# Clock_Segment.net
KiCad netlist of a schematic drawn in EAGLE
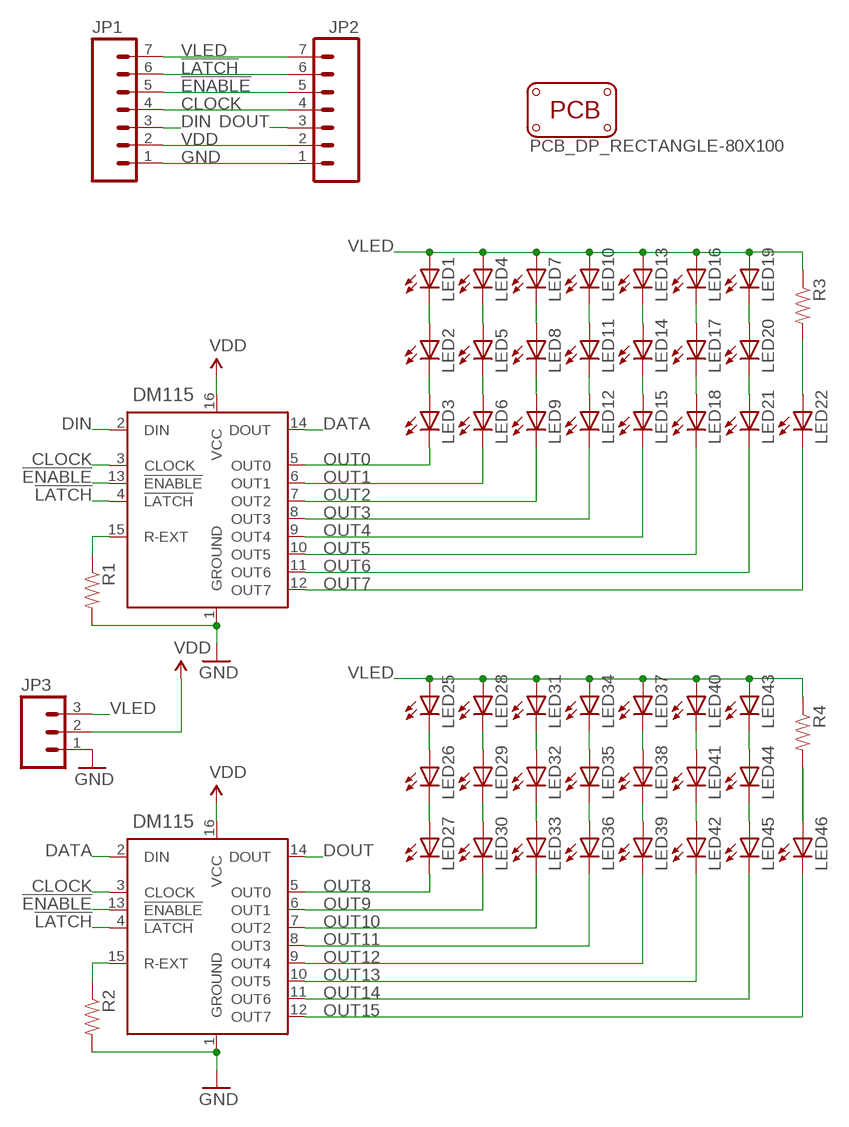
[diagram p0: schematic, sheet 1]

(export (version "E")
  (design (tool "Eeschema 10.0.6"))
  (components
    (comp (ref "JP1")
      (value "M07")
      (footprint "eagle-import:1X07")
      (libsource (lib "eagle-import") (part "M07"))
    )
    (comp (ref "JP2")
      (value "M07")
      (footprint "eagle-import:1X07")
      (libsource (lib "eagle-import") (part "M07"))
    )
    (comp (ref "JP3")
      (value "M03SCREW")
      (footprint "eagle-import:SCREWTERMINAL-3.5MM-3")
      (libsource (lib "eagle-import") (part "M03SCREW"))
    )
    (comp (ref "LED1")
      (value "LEDOVAL")
      (footprint "eagle-import:LED-OVAL")
      (libsource (lib "eagle-import") (part "LEDOVAL"))
    )
    (comp (ref "LED2")
      (value "LEDOVAL")
      (footprint "eagle-import:LED-OVAL")
      (libsource (lib "eagle-import") (part "LEDOVAL"))
    )
    (comp (ref "LED3")
      (value "LEDOVAL")
      (footprint "eagle-import:LED-OVAL")
      (libsource (lib "eagle-import") (part "LEDOVAL"))
    )
    (comp (ref "LED4")
      (value "LEDOVAL")
      (footprint "eagle-import:LED-OVAL")
      (libsource (lib "eagle-import") (part "LEDOVAL"))
    )
    (comp (ref "LED5")
      (value "LEDOVAL")
      (footprint "eagle-import:LED-OVAL")
      (libsource (lib "eagle-import") (part "LEDOVAL"))
    )
    (comp (ref "LED6")
      (value "LEDOVAL")
      (footprint "eagle-import:LED-OVAL")
      (libsource (lib "eagle-import") (part "LEDOVAL"))
    )
    (comp (ref "LED7")
      (value "LEDOVAL")
      (footprint "eagle-import:LED-OVAL")
      (libsource (lib "eagle-import") (part "LEDOVAL"))
    )
    (comp (ref "LED8")
      (value "LEDOVAL")
      (footprint "eagle-import:LED-OVAL")
      (libsource (lib "eagle-import") (part "LEDOVAL"))
    )
    (comp (ref "LED9")
      (value "LEDOVAL")
      (footprint "eagle-import:LED-OVAL")
      (libsource (lib "eagle-import") (part "LEDOVAL"))
    )
    (comp (ref "LED10")
      (value "LEDOVAL")
      (footprint "eagle-import:LED-OVAL")
      (libsource (lib "eagle-import") (part "LEDOVAL"))
    )
    (comp (ref "LED11")
      (value "LEDOVAL")
      (footprint "eagle-import:LED-OVAL")
      (libsource (lib "eagle-import") (part "LEDOVAL"))
    )
    (comp (ref "LED12")
      (value "LEDOVAL")
      (footprint "eagle-import:LED-OVAL")
      (libsource (lib "eagle-import") (part "LEDOVAL"))
    )
    (comp (ref "LED13")
      (value "LEDOVAL")
      (footprint "eagle-import:LED-OVAL")
      (libsource (lib "eagle-import") (part "LEDOVAL"))
    )
    (comp (ref "LED14")
      (value "LEDOVAL")
      (footprint "eagle-import:LED-OVAL")
      (libsource (lib "eagle-import") (part "LEDOVAL"))
    )
    (comp (ref "LED15")
      (value "LEDOVAL")
      (footprint "eagle-import:LED-OVAL")
      (libsource (lib "eagle-import") (part "LEDOVAL"))
    )
    (comp (ref "LED16")
      (value "LEDOVAL")
      (footprint "eagle-import:LED-OVAL")
      (libsource (lib "eagle-import") (part "LEDOVAL"))
    )
    (comp (ref "LED17")
      (value "LEDOVAL")
      (footprint "eagle-import:LED-OVAL")
      (libsource (lib "eagle-import") (part "LEDOVAL"))
    )
    (comp (ref "LED18")
      (value "LEDOVAL")
      (footprint "eagle-import:LED-OVAL")
      (libsource (lib "eagle-import") (part "LEDOVAL"))
    )
    (comp (ref "LED19")
      (value "LEDOVAL")
      (footprint "eagle-import:LED-OVAL")
      (libsource (lib "eagle-import") (part "LEDOVAL"))
    )
    (comp (ref "LED20")
      (value "LEDOVAL")
      (footprint "eagle-import:LED-OVAL")
      (libsource (lib "eagle-import") (part "LEDOVAL"))
    )
    (comp (ref "LED21")
      (value "LEDOVAL")
      (footprint "eagle-import:LED-OVAL")
      (libsource (lib "eagle-import") (part "LEDOVAL"))
    )
    (comp (ref "LED22")
      (value "LEDOVAL")
      (footprint "eagle-import:LED-OVAL")
      (libsource (lib "eagle-import") (part "LEDOVAL"))
    )
    (comp (ref "LED25")
      (value "LEDOVAL")
      (footprint "eagle-import:LED-OVAL")
      (libsource (lib "eagle-import") (part "LEDOVAL"))
    )
    (comp (ref "LED26")
      (value "LEDOVAL")
      (footprint "eagle-import:LED-OVAL")
      (libsource (lib "eagle-import") (part "LEDOVAL"))
    )
    (comp (ref "LED27")
      (value "LEDOVAL")
      (footprint "eagle-import:LED-OVAL")
      (libsource (lib "eagle-import") (part "LEDOVAL"))
    )
    (comp (ref "LED28")
      (value "LEDOVAL")
      (footprint "eagle-import:LED-OVAL")
      (libsource (lib "eagle-import") (part "LEDOVAL"))
    )
    (comp (ref "LED29")
      (value "LEDOVAL")
      (footprint "eagle-import:LED-OVAL")
      (libsource (lib "eagle-import") (part "LEDOVAL"))
    )
    (comp (ref "LED30")
      (value "LEDOVAL")
      (footprint "eagle-import:LED-OVAL")
      (libsource (lib "eagle-import") (part "LEDOVAL"))
    )
    (comp (ref "LED31")
      (value "LEDOVAL")
      (footprint "eagle-import:LED-OVAL")
      (libsource (lib "eagle-import") (part "LEDOVAL"))
    )
    (comp (ref "LED32")
      (value "LEDOVAL")
      (footprint "eagle-import:LED-OVAL")
      (libsource (lib "eagle-import") (part "LEDOVAL"))
    )
    (comp (ref "LED33")
      (value "LEDOVAL")
      (footprint "eagle-import:LED-OVAL")
      (libsource (lib "eagle-import") (part "LEDOVAL"))
    )
    (comp (ref "LED34")
      (value "LEDOVAL")
      (footprint "eagle-import:LED-OVAL")
      (libsource (lib "eagle-import") (part "LEDOVAL"))
    )
    (comp (ref "LED35")
      (value "LEDOVAL")
      (footprint "eagle-import:LED-OVAL")
      (libsource (lib "eagle-import") (part "LEDOVAL"))
    )
    (comp (ref "LED36")
      (value "LEDOVAL")
      (footprint "eagle-import:LED-OVAL")
      (libsource (lib "eagle-import") (part "LEDOVAL"))
    )
    (comp (ref "LED37")
      (value "LEDOVAL")
      (footprint "eagle-import:LED-OVAL")
      (libsource (lib "eagle-import") (part "LEDOVAL"))
    )
    (comp (ref "LED38")
      (value "LEDOVAL")
      (footprint "eagle-import:LED-OVAL")
      (libsource (lib "eagle-import") (part "LEDOVAL"))
    )
    (comp (ref "LED39")
      (value "LEDOVAL")
      (footprint "eagle-import:LED-OVAL")
      (libsource (lib "eagle-import") (part "LEDOVAL"))
    )
    (comp (ref "LED40")
      (value "LEDOVAL")
      (footprint "eagle-import:LED-OVAL")
      (libsource (lib "eagle-import") (part "LEDOVAL"))
    )
    (comp (ref "LED41")
      (value "LEDOVAL")
      (footprint "eagle-import:LED-OVAL")
      (libsource (lib "eagle-import") (part "LEDOVAL"))
    )
    (comp (ref "LED42")
      (value "LEDOVAL")
      (footprint "eagle-import:LED-OVAL")
      (libsource (lib "eagle-import") (part "LEDOVAL"))
    )
    (comp (ref "LED43")
      (value "LEDOVAL")
      (footprint "eagle-import:LED-OVAL")
      (libsource (lib "eagle-import") (part "LEDOVAL"))
    )
    (comp (ref "LED44")
      (value "LEDOVAL")
      (footprint "eagle-import:LED-OVAL")
      (libsource (lib "eagle-import") (part "LEDOVAL"))
    )
    (comp (ref "LED45")
      (value "LEDOVAL")
      (footprint "eagle-import:LED-OVAL")
      (libsource (lib "eagle-import") (part "LEDOVAL"))
    )
    (comp (ref "LED46")
      (value "LEDOVAL")
      (footprint "eagle-import:LED-OVAL")
      (libsource (lib "eagle-import") (part "LEDOVAL"))
    )
    (comp (ref "PCB1")
      (value "PCB_DP_RECTANGLE-80X100")
      (footprint "eagle-import:DP10080_V1")
      (libsource (lib "eagle-import") (part "PCB_DP_RECTANGLE-80X100"))
    )
    (comp (ref "R1")
      (value "RESISTORAXIAL-0.3")
      (footprint "eagle-import:AXIAL-0.3")
      (libsource (lib "eagle-import") (part "RESISTORAXIAL-0.3"))
    )
    (comp (ref "R2")
      (value "RESISTORAXIAL-0.3")
      (footprint "eagle-import:AXIAL-0.3")
      (libsource (lib "eagle-import") (part "RESISTORAXIAL-0.3"))
    )
    (comp (ref "R3")
      (value "RESISTORAXIAL-0.3")
      (footprint "eagle-import:AXIAL-0.3")
      (libsource (lib "eagle-import") (part "RESISTORAXIAL-0.3"))
    )
    (comp (ref "R4")
      (value "RESISTORAXIAL-0.3")
      (footprint "eagle-import:AXIAL-0.3")
      (libsource (lib "eagle-import") (part "RESISTORAXIAL-0.3"))
    )
    (comp (ref "U1")
      (value "DM115DIP16")
      (footprint "eagle-import:DIL16")
      (libsource (lib "eagle-import") (part "DM115DIP16"))
    )
    (comp (ref "U2")
      (value "DM115DIP16")
      (footprint "eagle-import:DIL16")
      (libsource (lib "eagle-import") (part "DM115DIP16"))
    )
  )
  (nets
    (net (code "1") (name "/CLOCK") (class "Default")
      (node (ref "JP1") (pin "4") (pinfunction "4_4") (pintype "passive"))
      (node (ref "JP2") (pin "4") (pinfunction "4_4") (pintype "passive"))
      (node (ref "U1") (pin "3") (pinfunction "CLOCK_3") (pintype "bidirectional"))
      (node (ref "U2") (pin "3") (pinfunction "CLOCK_3") (pintype "bidirectional"))
    )
    (net (code "2") (name "/DATA") (class "Default")
      (node (ref "U1") (pin "14") (pinfunction "DOUT_14") (pintype "bidirectional"))
      (node (ref "U2") (pin "2") (pinfunction "DIN_2") (pintype "bidirectional"))
    )
    (net (code "3") (name "/DIN") (class "Default")
      (node (ref "JP1") (pin "3") (pinfunction "3_3") (pintype "passive"))
      (node (ref "U1") (pin "2") (pinfunction "DIN_2") (pintype "bidirectional"))
    )
    (net (code "4") (name "/DOUT") (class "Default")
      (node (ref "JP2") (pin "3") (pinfunction "3_3") (pintype "passive"))
      (node (ref "U2") (pin "14") (pinfunction "DOUT_14") (pintype "bidirectional"))
    )
    (net (code "5") (name "/OUT0") (class "Default")
      (node (ref "LED3") (pin "CATHODE") (pinfunction "C_CATHODE") (pintype "passive"))
      (node (ref "U1") (pin "5") (pinfunction "OUT0_5") (pintype "bidirectional"))
    )
    (net (code "6") (name "/OUT1") (class "Default")
      (node (ref "LED6") (pin "CATHODE") (pinfunction "C_CATHODE") (pintype "passive"))
      (node (ref "U1") (pin "6") (pinfunction "OUT1_6") (pintype "bidirectional"))
    )
    (net (code "7") (name "/OUT2") (class "Default")
      (node (ref "LED9") (pin "CATHODE") (pinfunction "C_CATHODE") (pintype "passive"))
      (node (ref "U1") (pin "7") (pinfunction "OUT2_7") (pintype "bidirectional"))
    )
    (net (code "8") (name "/OUT3") (class "Default")
      (node (ref "LED12") (pin "CATHODE") (pinfunction "C_CATHODE") (pintype "passive"))
      (node (ref "U1") (pin "8") (pinfunction "OUT3_8") (pintype "bidirectional"))
    )
    (net (code "9") (name "/OUT4") (class "Default")
      (node (ref "LED15") (pin "CATHODE") (pinfunction "C_CATHODE") (pintype "passive"))
      (node (ref "U1") (pin "9") (pinfunction "OUT4_9") (pintype "bidirectional"))
    )
    (net (code "10") (name "/OUT5") (class "Default")
      (node (ref "LED18") (pin "CATHODE") (pinfunction "C_CATHODE") (pintype "passive"))
      (node (ref "U1") (pin "10") (pinfunction "OUT5_10") (pintype "bidirectional"))
    )
    (net (code "11") (name "/OUT6") (class "Default")
      (node (ref "LED21") (pin "CATHODE") (pinfunction "C_CATHODE") (pintype "passive"))
      (node (ref "U1") (pin "11") (pinfunction "OUT6_11") (pintype "bidirectional"))
    )
    (net (code "12") (name "/OUT7") (class "Default")
      (node (ref "LED22") (pin "CATHODE") (pinfunction "C_CATHODE") (pintype "passive"))
      (node (ref "U1") (pin "12") (pinfunction "OUT7_12") (pintype "bidirectional"))
    )
    (net (code "13") (name "/OUT8") (class "Default")
      (node (ref "LED27") (pin "CATHODE") (pinfunction "C_CATHODE") (pintype "passive"))
      (node (ref "U2") (pin "5") (pinfunction "OUT0_5") (pintype "bidirectional"))
    )
    (net (code "14") (name "/OUT9") (class "Default")
      (node (ref "LED30") (pin "CATHODE") (pinfunction "C_CATHODE") (pintype "passive"))
      (node (ref "U2") (pin "6") (pinfunction "OUT1_6") (pintype "bidirectional"))
    )
    (net (code "15") (name "/OUT10") (class "Default")
      (node (ref "LED33") (pin "CATHODE") (pinfunction "C_CATHODE") (pintype "passive"))
      (node (ref "U2") (pin "7") (pinfunction "OUT2_7") (pintype "bidirectional"))
    )
    (net (code "16") (name "/OUT11") (class "Default")
      (node (ref "LED36") (pin "CATHODE") (pinfunction "C_CATHODE") (pintype "passive"))
      (node (ref "U2") (pin "8") (pinfunction "OUT3_8") (pintype "bidirectional"))
    )
    (net (code "17") (name "/OUT12") (class "Default")
      (node (ref "LED39") (pin "CATHODE") (pinfunction "C_CATHODE") (pintype "passive"))
      (node (ref "U2") (pin "9") (pinfunction "OUT4_9") (pintype "bidirectional"))
    )
    (net (code "18") (name "/OUT13") (class "Default")
      (node (ref "LED42") (pin "CATHODE") (pinfunction "C_CATHODE") (pintype "passive"))
      (node (ref "U2") (pin "10") (pinfunction "OUT5_10") (pintype "bidirectional"))
    )
    (net (code "19") (name "/OUT14") (class "Default")
      (node (ref "LED45") (pin "CATHODE") (pinfunction "C_CATHODE") (pintype "passive"))
      (node (ref "U2") (pin "11") (pinfunction "OUT6_11") (pintype "bidirectional"))
    )
    (net (code "20") (name "/OUT15") (class "Default")
      (node (ref "LED46") (pin "CATHODE") (pinfunction "C_CATHODE") (pintype "passive"))
      (node (ref "U2") (pin "12") (pinfunction "OUT7_12") (pintype "bidirectional"))
    )
    (net (code "21") (name "/VLED") (class "Default")
      (node (ref "JP1") (pin "7") (pinfunction "7_7") (pintype "passive"))
      (node (ref "JP2") (pin "7") (pinfunction "7_7") (pintype "passive"))
      (node (ref "JP3") (pin "3") (pinfunction "3_3") (pintype "passive"))
      (node (ref "LED1") (pin "ANODE") (pinfunction "A_ANODE") (pintype "passive"))
      (node (ref "LED10") (pin "ANODE") (pinfunction "A_ANODE") (pintype "passive"))
      (node (ref "LED13") (pin "ANODE") (pinfunction "A_ANODE") (pintype "passive"))
      (node (ref "LED16") (pin "ANODE") (pinfunction "A_ANODE") (pintype "passive"))
      (node (ref "LED19") (pin "ANODE") (pinfunction "A_ANODE") (pintype "passive"))
      (node (ref "LED25") (pin "ANODE") (pinfunction "A_ANODE") (pintype "passive"))
      (node (ref "LED28") (pin "ANODE") (pinfunction "A_ANODE") (pintype "passive"))
      (node (ref "LED31") (pin "ANODE") (pinfunction "A_ANODE") (pintype "passive"))
      (node (ref "LED34") (pin "ANODE") (pinfunction "A_ANODE") (pintype "passive"))
      (node (ref "LED37") (pin "ANODE") (pinfunction "A_ANODE") (pintype "passive"))
      (node (ref "LED4") (pin "ANODE") (pinfunction "A_ANODE") (pintype "passive"))
      (node (ref "LED40") (pin "ANODE") (pinfunction "A_ANODE") (pintype "passive"))
      (node (ref "LED43") (pin "ANODE") (pinfunction "A_ANODE") (pintype "passive"))
      (node (ref "LED7") (pin "ANODE") (pinfunction "A_ANODE") (pintype "passive"))
      (node (ref "R3") (pin "P$1") (pinfunction "1_P$1") (pintype "passive"))
      (node (ref "R4") (pin "P$1") (pinfunction "1_P$1") (pintype "passive"))
    )
    (net (code "22") (name "/~{ENABLE}") (class "Default")
      (node (ref "JP1") (pin "5") (pinfunction "5_5") (pintype "passive"))
      (node (ref "JP2") (pin "5") (pinfunction "5_5") (pintype "passive"))
      (node (ref "U1") (pin "13") (pinfunction "~{ENABLE}_13") (pintype "bidirectional"))
      (node (ref "U2") (pin "13") (pinfunction "~{ENABLE}_13") (pintype "bidirectional"))
    )
    (net (code "23") (name "/~{LATCH}") (class "Default")
      (node (ref "JP1") (pin "6") (pinfunction "6_6") (pintype "passive"))
      (node (ref "JP2") (pin "6") (pinfunction "6_6") (pintype "passive"))
      (node (ref "U1") (pin "4") (pinfunction "~{LATCH}_4") (pintype "bidirectional"))
      (node (ref "U2") (pin "4") (pinfunction "~{LATCH}_4") (pintype "bidirectional"))
    )
    (net (code "24") (name "GND") (class "Default")
      (node (ref "JP1") (pin "1") (pinfunction "1_1") (pintype "passive"))
      (node (ref "JP2") (pin "1") (pinfunction "1_1") (pintype "passive"))
      (node (ref "JP3") (pin "1") (pinfunction "1_1") (pintype "passive"))
      (node (ref "R1") (pin "P$2") (pinfunction "2_P$2") (pintype "passive"))
      (node (ref "R2") (pin "P$2") (pinfunction "2_P$2") (pintype "passive"))
      (node (ref "U1") (pin "1") (pinfunction "GROUND_1") (pintype "bidirectional"))
      (node (ref "U2") (pin "1") (pinfunction "GROUND_1") (pintype "bidirectional"))
    )
    (net (code "25") (name "Net-(LED1-C)") (class "Default")
      (node (ref "LED1") (pin "CATHODE") (pinfunction "C_CATHODE") (pintype "passive"))
      (node (ref "LED2") (pin "ANODE") (pinfunction "A_ANODE") (pintype "passive"))
    )
    (net (code "26") (name "Net-(LED2-C)") (class "Default")
      (node (ref "LED2") (pin "CATHODE") (pinfunction "C_CATHODE") (pintype "passive"))
      (node (ref "LED3") (pin "ANODE") (pinfunction "A_ANODE") (pintype "passive"))
    )
    (net (code "27") (name "Net-(LED4-C)") (class "Default")
      (node (ref "LED4") (pin "CATHODE") (pinfunction "C_CATHODE") (pintype "passive"))
      (node (ref "LED5") (pin "ANODE") (pinfunction "A_ANODE") (pintype "passive"))
    )
    (net (code "28") (name "Net-(LED5-C)") (class "Default")
      (node (ref "LED5") (pin "CATHODE") (pinfunction "C_CATHODE") (pintype "passive"))
      (node (ref "LED6") (pin "ANODE") (pinfunction "A_ANODE") (pintype "passive"))
    )
    (net (code "29") (name "Net-(LED7-C)") (class "Default")
      (node (ref "LED7") (pin "CATHODE") (pinfunction "C_CATHODE") (pintype "passive"))
      (node (ref "LED8") (pin "ANODE") (pinfunction "A_ANODE") (pintype "passive"))
    )
    (net (code "30") (name "Net-(LED8-C)") (class "Default")
      (node (ref "LED8") (pin "CATHODE") (pinfunction "C_CATHODE") (pintype "passive"))
      (node (ref "LED9") (pin "ANODE") (pinfunction "A_ANODE") (pintype "passive"))
    )
    (net (code "31") (name "Net-(LED10-C)") (class "Default")
      (node (ref "LED10") (pin "CATHODE") (pinfunction "C_CATHODE") (pintype "passive"))
      (node (ref "LED11") (pin "ANODE") (pinfunction "A_ANODE") (pintype "passive"))
    )
    (net (code "32") (name "Net-(LED11-C)") (class "Default")
      (node (ref "LED11") (pin "CATHODE") (pinfunction "C_CATHODE") (pintype "passive"))
      (node (ref "LED12") (pin "ANODE") (pinfunction "A_ANODE") (pintype "passive"))
    )
    (net (code "33") (name "Net-(LED13-C)") (class "Default")
      (node (ref "LED13") (pin "CATHODE") (pinfunction "C_CATHODE") (pintype "passive"))
      (node (ref "LED14") (pin "ANODE") (pinfunction "A_ANODE") (pintype "passive"))
    )
    (net (code "34") (name "Net-(LED14-C)") (class "Default")
      (node (ref "LED14") (pin "CATHODE") (pinfunction "C_CATHODE") (pintype "passive"))
      (node (ref "LED15") (pin "ANODE") (pinfunction "A_ANODE") (pintype "passive"))
    )
    (net (code "35") (name "Net-(LED16-C)") (class "Default")
      (node (ref "LED16") (pin "CATHODE") (pinfunction "C_CATHODE") (pintype "passive"))
      (node (ref "LED17") (pin "ANODE") (pinfunction "A_ANODE") (pintype "passive"))
    )
    (net (code "36") (name "Net-(LED17-C)") (class "Default")
      (node (ref "LED17") (pin "CATHODE") (pinfunction "C_CATHODE") (pintype "passive"))
      (node (ref "LED18") (pin "ANODE") (pinfunction "A_ANODE") (pintype "passive"))
    )
    (net (code "37") (name "Net-(LED19-C)") (class "Default")
      (node (ref "LED19") (pin "CATHODE") (pinfunction "C_CATHODE") (pintype "passive"))
      (node (ref "LED20") (pin "ANODE") (pinfunction "A_ANODE") (pintype "passive"))
    )
    (net (code "38") (name "Net-(LED20-C)") (class "Default")
      (node (ref "LED20") (pin "CATHODE") (pinfunction "C_CATHODE") (pintype "passive"))
      (node (ref "LED21") (pin "ANODE") (pinfunction "A_ANODE") (pintype "passive"))
    )
    (net (code "39") (name "Net-(LED22-A)") (class "Default")
      (node (ref "LED22") (pin "ANODE") (pinfunction "A_ANODE") (pintype "passive"))
      (node (ref "R3") (pin "P$2") (pinfunction "2_P$2") (pintype "passive"))
    )
    (net (code "40") (name "Net-(LED25-C)") (class "Default")
      (node (ref "LED25") (pin "CATHODE") (pinfunction "C_CATHODE") (pintype "passive"))
      (node (ref "LED26") (pin "ANODE") (pinfunction "A_ANODE") (pintype "passive"))
    )
    (net (code "41") (name "Net-(LED26-C)") (class "Default")
      (node (ref "LED26") (pin "CATHODE") (pinfunction "C_CATHODE") (pintype "passive"))
      (node (ref "LED27") (pin "ANODE") (pinfunction "A_ANODE") (pintype "passive"))
    )
    (net (code "42") (name "Net-(LED28-C)") (class "Default")
      (node (ref "LED28") (pin "CATHODE") (pinfunction "C_CATHODE") (pintype "passive"))
      (node (ref "LED29") (pin "ANODE") (pinfunction "A_ANODE") (pintype "passive"))
    )
    (net (code "43") (name "Net-(LED29-C)") (class "Default")
      (node (ref "LED29") (pin "CATHODE") (pinfunction "C_CATHODE") (pintype "passive"))
      (node (ref "LED30") (pin "ANODE") (pinfunction "A_ANODE") (pintype "passive"))
    )
    (net (code "44") (name "Net-(LED31-C)") (class "Default")
      (node (ref "LED31") (pin "CATHODE") (pinfunction "C_CATHODE") (pintype "passive"))
      (node (ref "LED32") (pin "ANODE") (pinfunction "A_ANODE") (pintype "passive"))
    )
    (net (code "45") (name "Net-(LED32-C)") (class "Default")
      (node (ref "LED32") (pin "CATHODE") (pinfunction "C_CATHODE") (pintype "passive"))
      (node (ref "LED33") (pin "ANODE") (pinfunction "A_ANODE") (pintype "passive"))
    )
    (net (code "46") (name "Net-(LED34-C)") (class "Default")
      (node (ref "LED34") (pin "CATHODE") (pinfunction "C_CATHODE") (pintype "passive"))
      (node (ref "LED35") (pin "ANODE") (pinfunction "A_ANODE") (pintype "passive"))
    )
    (net (code "47") (name "Net-(LED35-C)") (class "Default")
      (node (ref "LED35") (pin "CATHODE") (pinfunction "C_CATHODE") (pintype "passive"))
      (node (ref "LED36") (pin "ANODE") (pinfunction "A_ANODE") (pintype "passive"))
    )
    (net (code "48") (name "Net-(LED37-C)") (class "Default")
      (node (ref "LED37") (pin "CATHODE") (pinfunction "C_CATHODE") (pintype "passive"))
      (node (ref "LED38") (pin "ANODE") (pinfunction "A_ANODE") (pintype "passive"))
    )
    (net (code "49") (name "Net-(LED38-C)") (class "Default")
      (node (ref "LED38") (pin "CATHODE") (pinfunction "C_CATHODE") (pintype "passive"))
      (node (ref "LED39") (pin "ANODE") (pinfunction "A_ANODE") (pintype "passive"))
    )
    (net (code "50") (name "Net-(LED40-C)") (class "Default")
      (node (ref "LED40") (pin "CATHODE") (pinfunction "C_CATHODE") (pintype "passive"))
      (node (ref "LED41") (pin "ANODE") (pinfunction "A_ANODE") (pintype "passive"))
    )
    (net (code "51") (name "Net-(LED41-C)") (class "Default")
      (node (ref "LED41") (pin "CATHODE") (pinfunction "C_CATHODE") (pintype "passive"))
      (node (ref "LED42") (pin "ANODE") (pinfunction "A_ANODE") (pintype "passive"))
    )
    (net (code "52") (name "Net-(LED43-C)") (class "Default")
      (node (ref "LED43") (pin "CATHODE") (pinfunction "C_CATHODE") (pintype "passive"))
      (node (ref "LED44") (pin "ANODE") (pinfunction "A_ANODE") (pintype "passive"))
    )
    (net (code "53") (name "Net-(LED44-C)") (class "Default")
      (node (ref "LED44") (pin "CATHODE") (pinfunction "C_CATHODE") (pintype "passive"))
      (node (ref "LED45") (pin "ANODE") (pinfunction "A_ANODE") (pintype "passive"))
    )
    (net (code "54") (name "Net-(LED46-A)") (class "Default")
      (node (ref "LED46") (pin "ANODE") (pinfunction "A_ANODE") (pintype "passive"))
      (node (ref "R4") (pin "P$2") (pinfunction "2_P$2") (pintype "passive"))
    )
    (net (code "55") (name "Net-(R1-1)") (class "Default")
      (node (ref "R1") (pin "P$1") (pinfunction "1_P$1") (pintype "passive"))
      (node (ref "U1") (pin "15") (pinfunction "R-EXT_15") (pintype "bidirectional"))
    )
    (net (code "56") (name "Net-(R2-1)") (class "Default")
      (node (ref "R2") (pin "P$1") (pinfunction "1_P$1") (pintype "passive"))
      (node (ref "U2") (pin "15") (pinfunction "R-EXT_15") (pintype "bidirectional"))
    )
    (net (code "57") (name "VDD") (class "Default")
      (node (ref "JP1") (pin "2") (pinfunction "2_2") (pintype "passive"))
      (node (ref "JP2") (pin "2") (pinfunction "2_2") (pintype "passive"))
      (node (ref "JP3") (pin "2") (pinfunction "2_2") (pintype "passive"))
      (node (ref "U1") (pin "16") (pinfunction "VCC_16") (pintype "bidirectional"))
      (node (ref "U2") (pin "16") (pinfunction "VCC_16") (pintype "bidirectional"))
    )
  )
)
